# NAQM_Node1.net
KiCad netlist of a schematic drawn in EAGLE
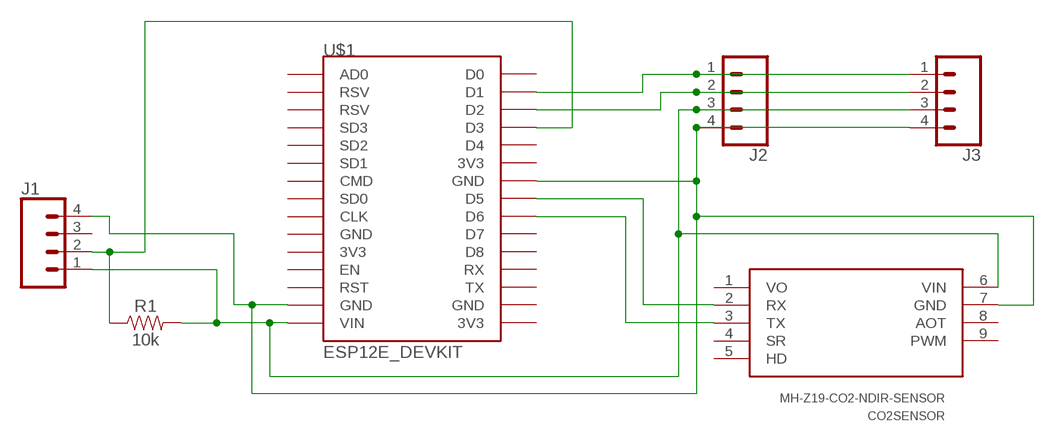
[diagram p0: schematic, sheet 1]

(export (version "E")
  (design (tool "Eeschema 10.0.6"))
  (components
    (comp (ref "CO2SENSOR")
      (value "MH-Z19-CO2-NDIR-SENSOR")
      (footprint "eagle-import:MH-Z19")
      (libsource (lib "eagle-import") (part "MH-Z19-CO2-NDIR-SENSOR"))
    )
    (comp (ref "J1")
      (value "CONN_04PTH")
      (footprint "eagle-import:1X04")
      (libsource (lib "eagle-import") (part "CONN_04PTH"))
    )
    (comp (ref "J2")
      (value "CONN_04PTH")
      (footprint "eagle-import:1X04")
      (libsource (lib "eagle-import") (part "CONN_04PTH"))
    )
    (comp (ref "J3")
      (value "CONN_04PTH")
      (footprint "eagle-import:1X04")
      (libsource (lib "eagle-import") (part "CONN_04PTH"))
    )
    (comp (ref "R1")
      (value "10k")
      (footprint "eagle-import:AXIAL-0.3")
      (libsource (lib "eagle-import") (part "10KOHM-HORIZ-1/4W-1%"))
    )
    (comp (ref "U$1")
      (value "ESP12E_DEVKIT")
      (footprint "eagle-import:ESP12E_DEVKIT")
      (libsource (lib "eagle-import") (part "ESP12E_DEVKIT"))
    )
  )
  (nets
    (net (code "1") (name "/VO") (class "Default")
      (node (ref "CO2SENSOR") (pin "1") (pinfunction "VO_1") (pintype "power_in"))
    )
    (net (code "2") (name "Net-(CO2SENSOR-GND)") (class "Default")
      (node (ref "CO2SENSOR") (pin "7") (pinfunction "GND_7") (pintype "power_in"))
      (node (ref "J1") (pin "4") (pinfunction "4_4") (pintype "passive"))
      (node (ref "J2") (pin "4") (pinfunction "4_4") (pintype "passive"))
      (node (ref "J3") (pin "4") (pinfunction "4_4") (pintype "passive"))
      (node (ref "U$1") (pin "GND@1") (pinfunction "GND_GND@1") (pintype "bidirectional"))
      (node (ref "U$1") (pin "GND@2") (pinfunction "GND_GND@2") (pintype "bidirectional"))
    )
    (net (code "3") (name "Net-(CO2SENSOR-RX)") (class "Default")
      (node (ref "CO2SENSOR") (pin "2") (pinfunction "RX_2") (pintype "input"))
      (node (ref "U$1") (pin "D5") (pinfunction "D5_D5") (pintype "bidirectional"))
    )
    (net (code "4") (name "Net-(CO2SENSOR-TX)") (class "Default")
      (node (ref "CO2SENSOR") (pin "3") (pinfunction "TX_3") (pintype "output"))
      (node (ref "U$1") (pin "D6") (pinfunction "D6_D6") (pintype "bidirectional"))
    )
    (net (code "5") (name "Net-(CO2SENSOR-VIN)") (class "Default")
      (node (ref "CO2SENSOR") (pin "6") (pinfunction "VIN_6") (pintype "power_in"))
      (node (ref "J1") (pin "1") (pinfunction "1_1") (pintype "passive"))
      (node (ref "J2") (pin "3") (pinfunction "3_3") (pintype "passive"))
      (node (ref "J3") (pin "3") (pinfunction "3_3") (pintype "passive"))
      (node (ref "R1") (pin "P$2") (pinfunction "2_P$2") (pintype "passive"))
      (node (ref "U$1") (pin "VIN") (pinfunction "VIN_VIN") (pintype "bidirectional"))
    )
    (net (code "6") (name "Net-(J2-Pad1)") (class "Default")
      (node (ref "J2") (pin "1") (pinfunction "1_1") (pintype "passive"))
      (node (ref "J3") (pin "1") (pinfunction "1_1") (pintype "passive"))
      (node (ref "U$1") (pin "D1") (pinfunction "D1_D1") (pintype "bidirectional"))
    )
    (net (code "7") (name "Net-(J2-Pad2)") (class "Default")
      (node (ref "J2") (pin "2") (pinfunction "2_2") (pintype "passive"))
      (node (ref "J3") (pin "2") (pinfunction "2_2") (pintype "passive"))
      (node (ref "U$1") (pin "D2") (pinfunction "D2_D2") (pintype "bidirectional"))
    )
    (net (code "8") (name "Net-(R1-1)") (class "Default")
      (node (ref "J1") (pin "2") (pinfunction "2_2") (pintype "passive"))
      (node (ref "R1") (pin "P$1") (pinfunction "1_P$1") (pintype "passive"))
      (node (ref "U$1") (pin "D3") (pinfunction "D3_D3") (pintype "bidirectional"))
    )
    (net (code "9") (name "unconnected-(CO2SENSOR-AOT-Pad8)") (class "Default")
      (node (ref "CO2SENSOR") (pin "8") (pinfunction "AOT_8") (pintype "no_connect"))
    )
    (net (code "10") (name "unconnected-(CO2SENSOR-HD-Pad5)") (class "Default")
      (node (ref "CO2SENSOR") (pin "5") (pinfunction "HD_5") (pintype "input"))
    )
    (net (code "11") (name "unconnected-(CO2SENSOR-PWM-Pad9)") (class "Default")
      (node (ref "CO2SENSOR") (pin "9") (pinfunction "PWM_9") (pintype "output"))
    )
    (net (code "12") (name "unconnected-(CO2SENSOR-SR-Pad4)") (class "Default")
      (node (ref "CO2SENSOR") (pin "4") (pinfunction "SR_4") (pintype "no_connect"))
    )
    (net (code "13") (name "unconnected-(J1-Pad3)") (class "Default")
      (node (ref "J1") (pin "3") (pinfunction "3_3") (pintype "passive"))
    )
    (net (code "14") (name "unconnected-(U$1-3V3-Pad3V3@0)") (class "Default")
      (node (ref "U$1") (pin "3V3@0") (pinfunction "3V3_3V3@0") (pintype "bidirectional"))
    )
    (net (code "15") (name "unconnected-(U$1-3V3-Pad3V3@1)") (class "Default")
      (node (ref "U$1") (pin "3V3@1") (pinfunction "3V3_3V3@1") (pintype "bidirectional"))
    )
    (net (code "16") (name "unconnected-(U$1-3V3-Pad3V3@2)") (class "Default")
      (node (ref "U$1") (pin "3V3@2") (pinfunction "3V3_3V3@2") (pintype "bidirectional"))
    )
    (net (code "17") (name "unconnected-(U$1-GND-PadGND@0)") (class "Default")
      (node (ref "U$1") (pin "GND@0") (pinfunction "GND_GND@0") (pintype "bidirectional"))
    )
    (net (code "18") (name "unconnected-(U$1-GND-PadGND@3)") (class "Default")
      (node (ref "U$1") (pin "GND@3") (pinfunction "GND_GND@3") (pintype "bidirectional"))
    )
    (net (code "19") (name "unconnected-(U$1-PadAD0)") (class "Default")
      (node (ref "U$1") (pin "AD0") (pinfunction "AD0_AD0") (pintype "bidirectional"))
    )
    (net (code "20") (name "unconnected-(U$1-PadCLK)") (class "Default")
      (node (ref "U$1") (pin "CLK") (pinfunction "CLK_CLK") (pintype "bidirectional"))
    )
    (net (code "21") (name "unconnected-(U$1-PadCMD)") (class "Default")
      (node (ref "U$1") (pin "CMD") (pinfunction "CMD_CMD") (pintype "bidirectional"))
    )
    (net (code "22") (name "unconnected-(U$1-PadD0)") (class "Default")
      (node (ref "U$1") (pin "D0") (pinfunction "D0_D0") (pintype "bidirectional"))
    )
    (net (code "23") (name "unconnected-(U$1-PadD4)") (class "Default")
      (node (ref "U$1") (pin "D4") (pinfunction "D4_D4") (pintype "bidirectional"))
    )
    (net (code "24") (name "unconnected-(U$1-PadD7)") (class "Default")
      (node (ref "U$1") (pin "D7") (pinfunction "D7_D7") (pintype "bidirectional"))
    )
    (net (code "25") (name "unconnected-(U$1-PadD8)") (class "Default")
      (node (ref "U$1") (pin "D8") (pinfunction "D8_D8") (pintype "bidirectional"))
    )
    (net (code "26") (name "unconnected-(U$1-PadEN)") (class "Default")
      (node (ref "U$1") (pin "EN") (pinfunction "EN_EN") (pintype "bidirectional"))
    )
    (net (code "27") (name "unconnected-(U$1-PadRST)") (class "Default")
      (node (ref "U$1") (pin "RST") (pinfunction "RST_RST") (pintype "bidirectional"))
    )
    (net (code "28") (name "unconnected-(U$1-PadRX)") (class "Default")
      (node (ref "U$1") (pin "RX") (pinfunction "RX_RX") (pintype "bidirectional"))
    )
    (net (code "29") (name "unconnected-(U$1-PadSD0)") (class "Default")
      (node (ref "U$1") (pin "SD0") (pinfunction "SD0_SD0") (pintype "bidirectional"))
    )
    (net (code "30") (name "unconnected-(U$1-PadSD1)") (class "Default")
      (node (ref "U$1") (pin "SD1") (pinfunction "SD1_SD1") (pintype "bidirectional"))
    )
    (net (code "31") (name "unconnected-(U$1-PadSD2)") (class "Default")
      (node (ref "U$1") (pin "SD2") (pinfunction "SD2_SD2") (pintype "bidirectional"))
    )
    (net (code "32") (name "unconnected-(U$1-PadSD3)") (class "Default")
      (node (ref "U$1") (pin "SD3") (pinfunction "SD3_SD3") (pintype "bidirectional"))
    )
    (net (code "33") (name "unconnected-(U$1-PadTX)") (class "Default")
      (node (ref "U$1") (pin "TX") (pinfunction "TX_TX") (pintype "bidirectional"))
    )
    (net (code "34") (name "unconnected-(U$1-RSV-PadRSV@0)") (class "Default")
      (node (ref "U$1") (pin "RSV@0") (pinfunction "RSV_RSV@0") (pintype "bidirectional"))
    )
    (net (code "35") (name "unconnected-(U$1-RSV-PadRSV@1)") (class "Default")
      (node (ref "U$1") (pin "RSV@1") (pinfunction "RSV_RSV@1") (pintype "bidirectional"))
    )
  )
)
